# pogoToProg.net
KiCad netlist of a schematic drawn in EAGLE
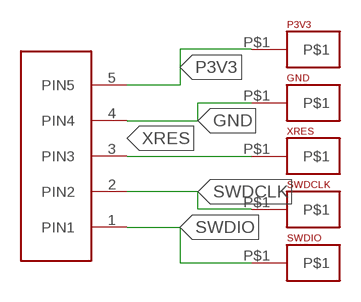
[diagram p0: schematic, sheet 1]

(export (version "E")
  (design (tool "Eeschema 10.0.6"))
  (components
    (comp (ref "GND")
      (value "POGO-MATING")
      (footprint "eagle-import:POGO-MATING")
      (libsource (lib "eagle-import") (part "POGO-MATING"))
    )
    (comp (ref "P3V3")
      (value "POGO-MATING")
      (footprint "eagle-import:POGO-MATING")
      (libsource (lib "eagle-import") (part "POGO-MATING"))
    )
    (comp (ref "SWDCLK")
      (value "POGO-MATING")
      (footprint "eagle-import:POGO-MATING")
      (libsource (lib "eagle-import") (part "POGO-MATING"))
    )
    (comp (ref "SWDIO")
      (value "POGO-MATING")
      (footprint "eagle-import:POGO-MATING")
      (libsource (lib "eagle-import") (part "POGO-MATING"))
    )
    (comp (ref "U$1")
      (value "HEADER-5")
      (footprint "eagle-import:NON-5")
      (libsource (lib "eagle-import") (part "HEADER-5"))
    )
    (comp (ref "XRES")
      (value "POGO-MATING")
      (footprint "eagle-import:POGO-MATING")
      (libsource (lib "eagle-import") (part "POGO-MATING"))
    )
  )
  (nets
    (net (code "1") (name "GND") (class "Default")
      (node (ref "GND") (pin "P$1") (pinfunction "P$1_P$1") (pintype "bidirectional"))
      (node (ref "U$1") (pin "4") (pinfunction "PIN4_4") (pintype "bidirectional"))
    )
    (net (code "2") (name "P3V3") (class "Default")
      (node (ref "P3V3") (pin "P$1") (pinfunction "P$1_P$1") (pintype "bidirectional"))
      (node (ref "U$1") (pin "5") (pinfunction "PIN5_5") (pintype "bidirectional"))
    )
    (net (code "3") (name "SWDCLK") (class "Default")
      (node (ref "SWDCLK") (pin "P$1") (pinfunction "P$1_P$1") (pintype "bidirectional"))
      (node (ref "U$1") (pin "2") (pinfunction "PIN2_2") (pintype "bidirectional"))
    )
    (net (code "4") (name "SWDIO") (class "Default")
      (node (ref "SWDIO") (pin "P$1") (pinfunction "P$1_P$1") (pintype "bidirectional"))
      (node (ref "U$1") (pin "1") (pinfunction "PIN1_1") (pintype "bidirectional"))
    )
    (net (code "5") (name "XRES") (class "Default")
      (node (ref "U$1") (pin "3") (pinfunction "PIN3_3") (pintype "bidirectional"))
      (node (ref "XRES") (pin "P$1") (pinfunction "P$1_P$1") (pintype "bidirectional"))
    )
  )
)
